# D_Output.net
KiCad netlist of a schematic drawn in Altium Designer
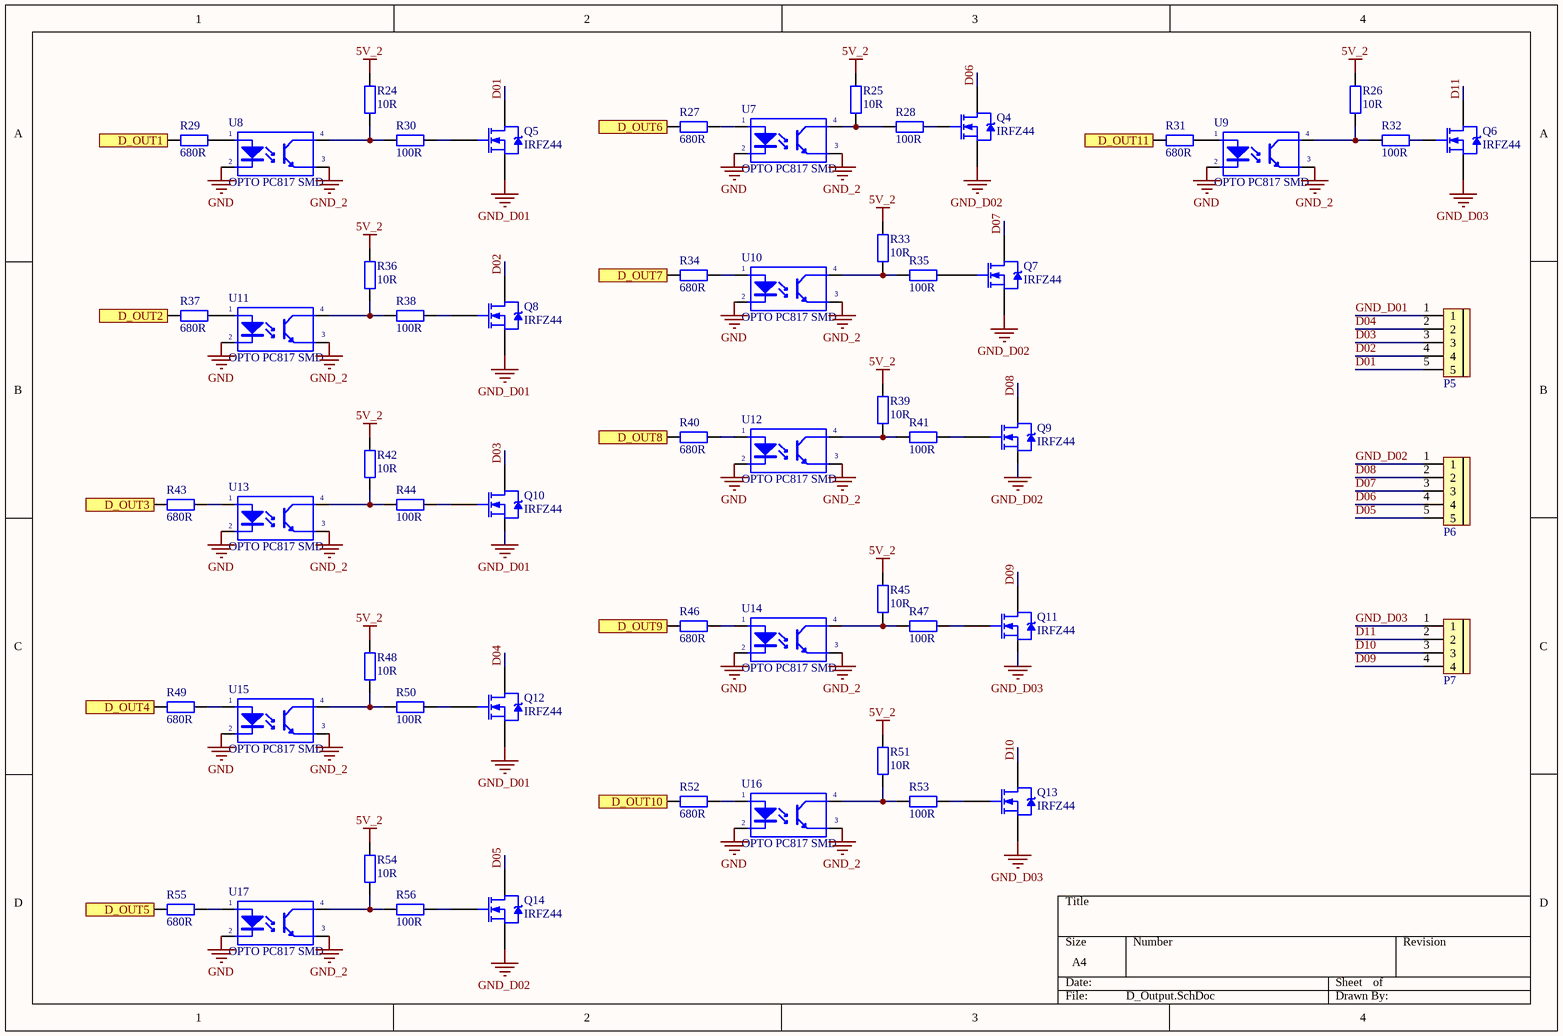
[diagram p0: D_Output.SchDoc]

(export (version "E")
  (design (tool "Eeschema 10.0.6"))
  (components
    (comp (ref "P5")
      (value "CON 5 EDG5.08")
      (footprint "CON 5 5EDG5.08")
      (description "Cắm")
      (libsource (lib "Altium_Lib_by_KhueNguyenCreator") (part "CON 5 EDG5.08"))
    )
    (comp (ref "P6")
      (value "CON 5 EDG5.08")
      (footprint "CON 5 5EDG5.08")
      (description "Cắm")
      (libsource (lib "Altium_Lib_by_KhueNguyenCreator") (part "CON 5 EDG5.08"))
    )
    (comp (ref "P7")
      (value "CON 4 EDG5.08")
      (footprint "CON 4 4EDG5.08")
      (description "Cắm")
      (libsource (lib "Altium_Lib_by_KhueNguyenCreator") (part "CON 4 EDG5.08"))
    )
    (comp (ref "Q4")
      (value "IRFZ44")
      (footprint "TO220")
      (description "N-Channel Power MOSFET")
      (libsource (lib "Altium_Lib_by_KhueNguyenCreator") (part "IRFZ44 DIP"))
    )
    (comp (ref "Q5")
      (value "IRFZ44")
      (footprint "TO220")
      (description "N-Channel Power MOSFET")
      (libsource (lib "Altium_Lib_by_KhueNguyenCreator") (part "IRFZ44 DIP"))
    )
    (comp (ref "Q6")
      (value "IRFZ44")
      (footprint "TO220")
      (description "N-Channel Power MOSFET")
      (libsource (lib "Altium_Lib_by_KhueNguyenCreator") (part "IRFZ44 DIP"))
    )
    (comp (ref "Q7")
      (value "IRFZ44")
      (footprint "TO220")
      (description "N-Channel Power MOSFET")
      (libsource (lib "Altium_Lib_by_KhueNguyenCreator") (part "IRFZ44 DIP"))
    )
    (comp (ref "Q8")
      (value "IRFZ44")
      (footprint "TO220")
      (description "N-Channel Power MOSFET")
      (libsource (lib "Altium_Lib_by_KhueNguyenCreator") (part "IRFZ44 DIP"))
    )
    (comp (ref "Q9")
      (value "IRFZ44")
      (footprint "TO220")
      (description "N-Channel Power MOSFET")
      (libsource (lib "Altium_Lib_by_KhueNguyenCreator") (part "IRFZ44 DIP"))
    )
    (comp (ref "Q10")
      (value "IRFZ44")
      (footprint "TO220")
      (description "N-Channel Power MOSFET")
      (libsource (lib "Altium_Lib_by_KhueNguyenCreator") (part "IRFZ44 DIP"))
    )
    (comp (ref "Q11")
      (value "IRFZ44")
      (footprint "TO220")
      (description "N-Channel Power MOSFET")
      (libsource (lib "Altium_Lib_by_KhueNguyenCreator") (part "IRFZ44 DIP"))
    )
    (comp (ref "Q12")
      (value "IRFZ44")
      (footprint "TO220")
      (description "N-Channel Power MOSFET")
      (libsource (lib "Altium_Lib_by_KhueNguyenCreator") (part "IRFZ44 DIP"))
    )
    (comp (ref "Q13")
      (value "IRFZ44")
      (footprint "TO220")
      (description "N-Channel Power MOSFET")
      (libsource (lib "Altium_Lib_by_KhueNguyenCreator") (part "IRFZ44 DIP"))
    )
    (comp (ref "Q14")
      (value "IRFZ44")
      (footprint "TO220")
      (description "N-Channel Power MOSFET")
      (libsource (lib "Altium_Lib_by_KhueNguyenCreator") (part "IRFZ44 DIP"))
    )
    (comp (ref "R24")
      (value "10R")
      (footprint "Tro smd 0603")
      (description "Dán")
      (libsource (lib "Altium_Lib_by_KhueNguyenCreator") (part "Tro 0603 5% 10R"))
    )
    (comp (ref "R25")
      (value "10R")
      (footprint "Tro smd 0603")
      (description "Dán")
      (libsource (lib "Altium_Lib_by_KhueNguyenCreator") (part "Tro 0603 5% 10R"))
    )
    (comp (ref "R26")
      (value "10R")
      (footprint "Tro smd 0603")
      (description "Dán")
      (libsource (lib "Altium_Lib_by_KhueNguyenCreator") (part "Tro 0603 5% 10R"))
    )
    (comp (ref "R27")
      (value "680R")
      (footprint "tro smd 0603")
      (description "Dán")
      (libsource (lib "Altium_Lib_by_KhueNguyenCreator") (part "Tro 0603 1% 680R"))
    )
    (comp (ref "R28")
      (value "100R")
      (footprint "tro smd 0603")
      (description "Dán")
      (libsource (lib "Altium_Lib_by_KhueNguyenCreator") (part "Tro 0603 5% 100R"))
    )
    (comp (ref "R29")
      (value "680R")
      (footprint "tro smd 0603")
      (description "Dán")
      (libsource (lib "Altium_Lib_by_KhueNguyenCreator") (part "Tro 0603 1% 680R"))
    )
    (comp (ref "R30")
      (value "100R")
      (footprint "tro smd 0603")
      (description "Dán")
      (libsource (lib "Altium_Lib_by_KhueNguyenCreator") (part "Tro 0603 5% 100R"))
    )
    (comp (ref "R31")
      (value "680R")
      (footprint "tro smd 0603")
      (description "Dán")
      (libsource (lib "Altium_Lib_by_KhueNguyenCreator") (part "Tro 0603 1% 680R"))
    )
    (comp (ref "R32")
      (value "100R")
      (footprint "tro smd 0603")
      (description "Dán")
      (libsource (lib "Altium_Lib_by_KhueNguyenCreator") (part "Tro 0603 5% 100R"))
    )
    (comp (ref "R33")
      (value "10R")
      (footprint "Tro smd 0603")
      (description "Dán")
      (libsource (lib "Altium_Lib_by_KhueNguyenCreator") (part "Tro 0603 5% 10R"))
    )
    (comp (ref "R34")
      (value "680R")
      (footprint "tro smd 0603")
      (description "Dán")
      (libsource (lib "Altium_Lib_by_KhueNguyenCreator") (part "Tro 0603 1% 680R"))
    )
    (comp (ref "R35")
      (value "100R")
      (footprint "tro smd 0603")
      (description "Dán")
      (libsource (lib "Altium_Lib_by_KhueNguyenCreator") (part "Tro 0603 5% 100R"))
    )
    (comp (ref "R36")
      (value "10R")
      (footprint "Tro smd 0603")
      (description "Dán")
      (libsource (lib "Altium_Lib_by_KhueNguyenCreator") (part "Tro 0603 5% 10R"))
    )
    (comp (ref "R37")
      (value "680R")
      (footprint "tro smd 0603")
      (description "Dán")
      (libsource (lib "Altium_Lib_by_KhueNguyenCreator") (part "Tro 0603 1% 680R"))
    )
    (comp (ref "R38")
      (value "100R")
      (footprint "tro smd 0603")
      (description "Dán")
      (libsource (lib "Altium_Lib_by_KhueNguyenCreator") (part "Tro 0603 5% 100R"))
    )
    (comp (ref "R39")
      (value "10R")
      (footprint "Tro smd 0603")
      (description "Dán")
      (libsource (lib "Altium_Lib_by_KhueNguyenCreator") (part "Tro 0603 5% 10R"))
    )
    (comp (ref "R40")
      (value "680R")
      (footprint "tro smd 0603")
      (description "Dán")
      (libsource (lib "Altium_Lib_by_KhueNguyenCreator") (part "Tro 0603 1% 680R"))
    )
    (comp (ref "R41")
      (value "100R")
      (footprint "tro smd 0603")
      (description "Dán")
      (libsource (lib "Altium_Lib_by_KhueNguyenCreator") (part "Tro 0603 5% 100R"))
    )
    (comp (ref "R42")
      (value "10R")
      (footprint "Tro smd 0603")
      (description "Dán")
      (libsource (lib "Altium_Lib_by_KhueNguyenCreator") (part "Tro 0603 5% 10R"))
    )
    (comp (ref "R43")
      (value "680R")
      (footprint "tro smd 0603")
      (description "Dán")
      (libsource (lib "Altium_Lib_by_KhueNguyenCreator") (part "Tro 0603 1% 680R"))
    )
    (comp (ref "R44")
      (value "100R")
      (footprint "tro smd 0603")
      (description "Dán")
      (libsource (lib "Altium_Lib_by_KhueNguyenCreator") (part "Tro 0603 5% 100R"))
    )
    (comp (ref "R45")
      (value "10R")
      (footprint "Tro smd 0603")
      (description "Dán")
      (libsource (lib "Altium_Lib_by_KhueNguyenCreator") (part "Tro 0603 5% 10R"))
    )
    (comp (ref "R46")
      (value "680R")
      (footprint "tro smd 0603")
      (description "Dán")
      (libsource (lib "Altium_Lib_by_KhueNguyenCreator") (part "Tro 0603 1% 680R"))
    )
    (comp (ref "R47")
      (value "100R")
      (footprint "tro smd 0603")
      (description "Dán")
      (libsource (lib "Altium_Lib_by_KhueNguyenCreator") (part "Tro 0603 5% 100R"))
    )
    (comp (ref "R48")
      (value "10R")
      (footprint "Tro smd 0603")
      (description "Dán")
      (libsource (lib "Altium_Lib_by_KhueNguyenCreator") (part "Tro 0603 5% 10R"))
    )
    (comp (ref "R49")
      (value "680R")
      (footprint "tro smd 0603")
      (description "Dán")
      (libsource (lib "Altium_Lib_by_KhueNguyenCreator") (part "Tro 0603 1% 680R"))
    )
    (comp (ref "R50")
      (value "100R")
      (footprint "tro smd 0603")
      (description "Dán")
      (libsource (lib "Altium_Lib_by_KhueNguyenCreator") (part "Tro 0603 5% 100R"))
    )
    (comp (ref "R51")
      (value "10R")
      (footprint "Tro smd 0603")
      (description "Dán")
      (libsource (lib "Altium_Lib_by_KhueNguyenCreator") (part "Tro 0603 5% 10R"))
    )
    (comp (ref "R52")
      (value "680R")
      (footprint "tro smd 0603")
      (description "Dán")
      (libsource (lib "Altium_Lib_by_KhueNguyenCreator") (part "Tro 0603 1% 680R"))
    )
    (comp (ref "R53")
      (value "100R")
      (footprint "tro smd 0603")
      (description "Dán")
      (libsource (lib "Altium_Lib_by_KhueNguyenCreator") (part "Tro 0603 5% 100R"))
    )
    (comp (ref "R54")
      (value "10R")
      (footprint "Tro smd 0603")
      (description "Dán")
      (libsource (lib "Altium_Lib_by_KhueNguyenCreator") (part "Tro 0603 5% 10R"))
    )
    (comp (ref "R55")
      (value "680R")
      (footprint "tro smd 0603")
      (description "Dán")
      (libsource (lib "Altium_Lib_by_KhueNguyenCreator") (part "Tro 0603 1% 680R"))
    )
    (comp (ref "R56")
      (value "100R")
      (footprint "tro smd 0603")
      (description "Dán")
      (libsource (lib "Altium_Lib_by_KhueNguyenCreator") (part "Tro 0603 5% 100R"))
    )
    (comp (ref "U7")
      (value "OPTO PC817 SMD")
      (footprint "SOP4")
      (description "Single Opto")
      (libsource (lib "Altium_Lib_by_KhueNguyenCreator") (part "OPTO PC817 SMD"))
    )
    (comp (ref "U8")
      (value "OPTO PC817 SMD")
      (footprint "SOP4")
      (description "Single Opto")
      (libsource (lib "Altium_Lib_by_KhueNguyenCreator") (part "OPTO PC817 SMD"))
    )
    (comp (ref "U9")
      (value "OPTO PC817 SMD")
      (footprint "SOP4")
      (description "Single Opto")
      (libsource (lib "Altium_Lib_by_KhueNguyenCreator") (part "OPTO PC817 SMD"))
    )
    (comp (ref "U10")
      (value "OPTO PC817 SMD")
      (footprint "SOP4")
      (description "Single Opto")
      (libsource (lib "Altium_Lib_by_KhueNguyenCreator") (part "OPTO PC817 SMD"))
    )
    (comp (ref "U11")
      (value "OPTO PC817 SMD")
      (footprint "SOP4")
      (description "Single Opto")
      (libsource (lib "Altium_Lib_by_KhueNguyenCreator") (part "OPTO PC817 SMD"))
    )
    (comp (ref "U12")
      (value "OPTO PC817 SMD")
      (footprint "SOP4")
      (description "Single Opto")
      (libsource (lib "Altium_Lib_by_KhueNguyenCreator") (part "OPTO PC817 SMD"))
    )
    (comp (ref "U13")
      (value "OPTO PC817 SMD")
      (footprint "SOP4")
      (description "Single Opto")
      (libsource (lib "Altium_Lib_by_KhueNguyenCreator") (part "OPTO PC817 SMD"))
    )
    (comp (ref "U14")
      (value "OPTO PC817 SMD")
      (footprint "SOP4")
      (description "Single Opto")
      (libsource (lib "Altium_Lib_by_KhueNguyenCreator") (part "OPTO PC817 SMD"))
    )
    (comp (ref "U15")
      (value "OPTO PC817 SMD")
      (footprint "SOP4")
      (description "Single Opto")
      (libsource (lib "Altium_Lib_by_KhueNguyenCreator") (part "OPTO PC817 SMD"))
    )
    (comp (ref "U16")
      (value "OPTO PC817 SMD")
      (footprint "SOP4")
      (description "Single Opto")
      (libsource (lib "Altium_Lib_by_KhueNguyenCreator") (part "OPTO PC817 SMD"))
    )
    (comp (ref "U17")
      (value "OPTO PC817 SMD")
      (footprint "SOP4")
      (description "Single Opto")
      (libsource (lib "Altium_Lib_by_KhueNguyenCreator") (part "OPTO PC817 SMD"))
    )
  )
  (nets
    (net (code "1") (name "/D01") (class "Default")
      (node (ref "P5") (pin "5") (pinfunction "5_5") (pintype "passive"))
      (node (ref "Q5") (pin "2") (pinfunction "D_2") (pintype "passive"))
    )
    (net (code "2") (name "/D02") (class "Default")
      (node (ref "P5") (pin "4") (pinfunction "4_4") (pintype "passive"))
      (node (ref "Q8") (pin "2") (pinfunction "D_2") (pintype "passive"))
    )
    (net (code "3") (name "/D03") (class "Default")
      (node (ref "P5") (pin "3") (pinfunction "3_3") (pintype "passive"))
      (node (ref "Q10") (pin "2") (pinfunction "D_2") (pintype "passive"))
    )
    (net (code "4") (name "/D04") (class "Default")
      (node (ref "P5") (pin "2") (pinfunction "2_2") (pintype "passive"))
      (node (ref "Q12") (pin "2") (pinfunction "D_2") (pintype "passive"))
    )
    (net (code "5") (name "/D05") (class "Default")
      (node (ref "P6") (pin "5") (pinfunction "5_5") (pintype "passive"))
      (node (ref "Q14") (pin "2") (pinfunction "D_2") (pintype "passive"))
    )
    (net (code "6") (name "/D06") (class "Default")
      (node (ref "P6") (pin "4") (pinfunction "4_4") (pintype "passive"))
      (node (ref "Q4") (pin "2") (pinfunction "D_2") (pintype "passive"))
    )
    (net (code "7") (name "/D07") (class "Default")
      (node (ref "P6") (pin "3") (pinfunction "3_3") (pintype "passive"))
      (node (ref "Q7") (pin "2") (pinfunction "D_2") (pintype "passive"))
    )
    (net (code "8") (name "/D08") (class "Default")
      (node (ref "P6") (pin "2") (pinfunction "2_2") (pintype "passive"))
      (node (ref "Q9") (pin "2") (pinfunction "D_2") (pintype "passive"))
    )
    (net (code "9") (name "/D09") (class "Default")
      (node (ref "P7") (pin "4") (pinfunction "4_4") (pintype "passive"))
      (node (ref "Q11") (pin "2") (pinfunction "D_2") (pintype "passive"))
    )
    (net (code "10") (name "/D10") (class "Default")
      (node (ref "P7") (pin "3") (pinfunction "3_3") (pintype "passive"))
      (node (ref "Q13") (pin "2") (pinfunction "D_2") (pintype "passive"))
    )
    (net (code "11") (name "/D11") (class "Default")
      (node (ref "P7") (pin "2") (pinfunction "2_2") (pintype "passive"))
      (node (ref "Q6") (pin "2") (pinfunction "D_2") (pintype "passive"))
    )
    (net (code "12") (name "/D_OUT1") (class "Default")
      (node (ref "R29") (pin "1") (pinfunction "1_1") (pintype "passive"))
    )
    (net (code "13") (name "/D_OUT2") (class "Default")
      (node (ref "R37") (pin "1") (pinfunction "1_1") (pintype "passive"))
    )
    (net (code "14") (name "/D_OUT3") (class "Default")
      (node (ref "R43") (pin "1") (pinfunction "1_1") (pintype "passive"))
    )
    (net (code "15") (name "/D_OUT4") (class "Default")
      (node (ref "R49") (pin "1") (pinfunction "1_1") (pintype "passive"))
    )
    (net (code "16") (name "/D_OUT5") (class "Default")
      (node (ref "R55") (pin "1") (pinfunction "1_1") (pintype "passive"))
    )
    (net (code "17") (name "/D_OUT6") (class "Default")
      (node (ref "R27") (pin "1") (pinfunction "1_1") (pintype "passive"))
    )
    (net (code "18") (name "/D_OUT7") (class "Default")
      (node (ref "R34") (pin "1") (pinfunction "1_1") (pintype "passive"))
    )
    (net (code "19") (name "/D_OUT8") (class "Default")
      (node (ref "R40") (pin "1") (pinfunction "1_1") (pintype "passive"))
    )
    (net (code "20") (name "/D_OUT9") (class "Default")
      (node (ref "R46") (pin "1") (pinfunction "1_1") (pintype "passive"))
    )
    (net (code "21") (name "/D_OUT10") (class "Default")
      (node (ref "R52") (pin "1") (pinfunction "1_1") (pintype "passive"))
    )
    (net (code "22") (name "/D_OUT11") (class "Default")
      (node (ref "R31") (pin "1") (pinfunction "1_1") (pintype "passive"))
    )
    (net (code "23") (name "5V_2") (class "Default")
      (node (ref "R24") (pin "2") (pinfunction "2_2") (pintype "passive"))
      (node (ref "R25") (pin "2") (pinfunction "2_2") (pintype "passive"))
      (node (ref "R26") (pin "2") (pinfunction "2_2") (pintype "passive"))
      (node (ref "R33") (pin "2") (pinfunction "2_2") (pintype "passive"))
      (node (ref "R36") (pin "2") (pinfunction "2_2") (pintype "passive"))
      (node (ref "R39") (pin "2") (pinfunction "2_2") (pintype "passive"))
      (node (ref "R42") (pin "2") (pinfunction "2_2") (pintype "passive"))
      (node (ref "R45") (pin "2") (pinfunction "2_2") (pintype "passive"))
      (node (ref "R48") (pin "2") (pinfunction "2_2") (pintype "passive"))
      (node (ref "R51") (pin "2") (pinfunction "2_2") (pintype "passive"))
      (node (ref "R54") (pin "2") (pinfunction "2_2") (pintype "passive"))
    )
    (net (code "24") (name "GND") (class "Default")
      (node (ref "U10") (pin "2") (pinfunction "K_2") (pintype "passive"))
      (node (ref "U11") (pin "2") (pinfunction "K_2") (pintype "passive"))
      (node (ref "U12") (pin "2") (pinfunction "K_2") (pintype "passive"))
      (node (ref "U13") (pin "2") (pinfunction "K_2") (pintype "passive"))
      (node (ref "U14") (pin "2") (pinfunction "K_2") (pintype "passive"))
      (node (ref "U15") (pin "2") (pinfunction "K_2") (pintype "passive"))
      (node (ref "U16") (pin "2") (pinfunction "K_2") (pintype "passive"))
      (node (ref "U17") (pin "2") (pinfunction "K_2") (pintype "passive"))
      (node (ref "U7") (pin "2") (pinfunction "K_2") (pintype "passive"))
      (node (ref "U8") (pin "2") (pinfunction "K_2") (pintype "passive"))
      (node (ref "U9") (pin "2") (pinfunction "K_2") (pintype "passive"))
    )
    (net (code "25") (name "GND_2") (class "Default")
      (node (ref "U10") (pin "3") (pinfunction "E_3") (pintype "passive"))
      (node (ref "U11") (pin "3") (pinfunction "E_3") (pintype "passive"))
      (node (ref "U12") (pin "3") (pinfunction "E_3") (pintype "passive"))
      (node (ref "U13") (pin "3") (pinfunction "E_3") (pintype "passive"))
      (node (ref "U14") (pin "3") (pinfunction "E_3") (pintype "passive"))
      (node (ref "U15") (pin "3") (pinfunction "E_3") (pintype "passive"))
      (node (ref "U16") (pin "3") (pinfunction "E_3") (pintype "passive"))
      (node (ref "U17") (pin "3") (pinfunction "E_3") (pintype "passive"))
      (node (ref "U7") (pin "3") (pinfunction "E_3") (pintype "passive"))
      (node (ref "U8") (pin "3") (pinfunction "E_3") (pintype "passive"))
      (node (ref "U9") (pin "3") (pinfunction "E_3") (pintype "passive"))
    )
    (net (code "26") (name "GND_D01") (class "Default")
      (node (ref "P5") (pin "1") (pinfunction "1_1") (pintype "passive"))
      (node (ref "Q10") (pin "3") (pinfunction "S_3") (pintype "passive"))
      (node (ref "Q12") (pin "3") (pinfunction "S_3") (pintype "passive"))
      (node (ref "Q5") (pin "3") (pinfunction "S_3") (pintype "passive"))
      (node (ref "Q8") (pin "3") (pinfunction "S_3") (pintype "passive"))
    )
    (net (code "27") (name "GND_D02") (class "Default")
      (node (ref "P6") (pin "1") (pinfunction "1_1") (pintype "passive"))
      (node (ref "Q14") (pin "3") (pinfunction "S_3") (pintype "passive"))
      (node (ref "Q4") (pin "3") (pinfunction "S_3") (pintype "passive"))
      (node (ref "Q7") (pin "3") (pinfunction "S_3") (pintype "passive"))
      (node (ref "Q9") (pin "3") (pinfunction "S_3") (pintype "passive"))
    )
    (net (code "28") (name "GND_D03") (class "Default")
      (node (ref "P7") (pin "1") (pinfunction "1_1") (pintype "passive"))
      (node (ref "Q11") (pin "3") (pinfunction "S_3") (pintype "passive"))
      (node (ref "Q13") (pin "3") (pinfunction "S_3") (pintype "passive"))
      (node (ref "Q6") (pin "3") (pinfunction "S_3") (pintype "passive"))
    )
    (net (code "29") (name "Net-(Q4-G)") (class "Default")
      (node (ref "Q4") (pin "1") (pinfunction "G_1") (pintype "passive"))
      (node (ref "R28") (pin "2") (pinfunction "2_2") (pintype "passive"))
    )
    (net (code "30") (name "Net-(Q5-G)") (class "Default")
      (node (ref "Q5") (pin "1") (pinfunction "G_1") (pintype "passive"))
      (node (ref "R30") (pin "2") (pinfunction "2_2") (pintype "passive"))
    )
    (net (code "31") (name "Net-(Q6-G)") (class "Default")
      (node (ref "Q6") (pin "1") (pinfunction "G_1") (pintype "passive"))
      (node (ref "R32") (pin "2") (pinfunction "2_2") (pintype "passive"))
    )
    (net (code "32") (name "Net-(Q7-G)") (class "Default")
      (node (ref "Q7") (pin "1") (pinfunction "G_1") (pintype "passive"))
      (node (ref "R35") (pin "2") (pinfunction "2_2") (pintype "passive"))
    )
    (net (code "33") (name "Net-(Q8-G)") (class "Default")
      (node (ref "Q8") (pin "1") (pinfunction "G_1") (pintype "passive"))
      (node (ref "R38") (pin "2") (pinfunction "2_2") (pintype "passive"))
    )
    (net (code "34") (name "Net-(Q9-G)") (class "Default")
      (node (ref "Q9") (pin "1") (pinfunction "G_1") (pintype "passive"))
      (node (ref "R41") (pin "2") (pinfunction "2_2") (pintype "passive"))
    )
    (net (code "35") (name "Net-(Q10-G)") (class "Default")
      (node (ref "Q10") (pin "1") (pinfunction "G_1") (pintype "passive"))
      (node (ref "R44") (pin "2") (pinfunction "2_2") (pintype "passive"))
    )
    (net (code "36") (name "Net-(Q11-G)") (class "Default")
      (node (ref "Q11") (pin "1") (pinfunction "G_1") (pintype "passive"))
      (node (ref "R47") (pin "2") (pinfunction "2_2") (pintype "passive"))
    )
    (net (code "37") (name "Net-(Q12-G)") (class "Default")
      (node (ref "Q12") (pin "1") (pinfunction "G_1") (pintype "passive"))
      (node (ref "R50") (pin "2") (pinfunction "2_2") (pintype "passive"))
    )
    (net (code "38") (name "Net-(Q13-G)") (class "Default")
      (node (ref "Q13") (pin "1") (pinfunction "G_1") (pintype "passive"))
      (node (ref "R53") (pin "2") (pinfunction "2_2") (pintype "passive"))
    )
    (net (code "39") (name "Net-(Q14-G)") (class "Default")
      (node (ref "Q14") (pin "1") (pinfunction "G_1") (pintype "passive"))
      (node (ref "R56") (pin "2") (pinfunction "2_2") (pintype "passive"))
    )
    (net (code "40") (name "Net-(U7-A)") (class "Default")
      (node (ref "R27") (pin "2") (pinfunction "2_2") (pintype "passive"))
      (node (ref "U7") (pin "1") (pinfunction "A_1") (pintype "passive"))
    )
    (net (code "41") (name "Net-(U7-C)") (class "Default")
      (node (ref "R25") (pin "1") (pinfunction "1_1") (pintype "passive"))
      (node (ref "R28") (pin "1") (pinfunction "1_1") (pintype "passive"))
      (node (ref "U7") (pin "4") (pinfunction "C_4") (pintype "passive"))
    )
    (net (code "42") (name "Net-(U8-A)") (class "Default")
      (node (ref "R29") (pin "2") (pinfunction "2_2") (pintype "passive"))
      (node (ref "U8") (pin "1") (pinfunction "A_1") (pintype "passive"))
    )
    (net (code "43") (name "Net-(U8-C)") (class "Default")
      (node (ref "R24") (pin "1") (pinfunction "1_1") (pintype "passive"))
      (node (ref "R30") (pin "1") (pinfunction "1_1") (pintype "passive"))
      (node (ref "U8") (pin "4") (pinfunction "C_4") (pintype "passive"))
    )
    (net (code "44") (name "Net-(U9-A)") (class "Default")
      (node (ref "R31") (pin "2") (pinfunction "2_2") (pintype "passive"))
      (node (ref "U9") (pin "1") (pinfunction "A_1") (pintype "passive"))
    )
    (net (code "45") (name "Net-(U9-C)") (class "Default")
      (node (ref "R26") (pin "1") (pinfunction "1_1") (pintype "passive"))
      (node (ref "R32") (pin "1") (pinfunction "1_1") (pintype "passive"))
      (node (ref "U9") (pin "4") (pinfunction "C_4") (pintype "passive"))
    )
    (net (code "46") (name "Net-(U10-A)") (class "Default")
      (node (ref "R34") (pin "2") (pinfunction "2_2") (pintype "passive"))
      (node (ref "U10") (pin "1") (pinfunction "A_1") (pintype "passive"))
    )
    (net (code "47") (name "Net-(U10-C)") (class "Default")
      (node (ref "R33") (pin "1") (pinfunction "1_1") (pintype "passive"))
      (node (ref "R35") (pin "1") (pinfunction "1_1") (pintype "passive"))
      (node (ref "U10") (pin "4") (pinfunction "C_4") (pintype "passive"))
    )
    (net (code "48") (name "Net-(U11-A)") (class "Default")
      (node (ref "R37") (pin "2") (pinfunction "2_2") (pintype "passive"))
      (node (ref "U11") (pin "1") (pinfunction "A_1") (pintype "passive"))
    )
    (net (code "49") (name "Net-(U11-C)") (class "Default")
      (node (ref "R36") (pin "1") (pinfunction "1_1") (pintype "passive"))
      (node (ref "R38") (pin "1") (pinfunction "1_1") (pintype "passive"))
      (node (ref "U11") (pin "4") (pinfunction "C_4") (pintype "passive"))
    )
    (net (code "50") (name "Net-(U12-A)") (class "Default")
      (node (ref "R40") (pin "2") (pinfunction "2_2") (pintype "passive"))
      (node (ref "U12") (pin "1") (pinfunction "A_1") (pintype "passive"))
    )
    (net (code "51") (name "Net-(U12-C)") (class "Default")
      (node (ref "R39") (pin "1") (pinfunction "1_1") (pintype "passive"))
      (node (ref "R41") (pin "1") (pinfunction "1_1") (pintype "passive"))
      (node (ref "U12") (pin "4") (pinfunction "C_4") (pintype "passive"))
    )
    (net (code "52") (name "Net-(U13-A)") (class "Default")
      (node (ref "R43") (pin "2") (pinfunction "2_2") (pintype "passive"))
      (node (ref "U13") (pin "1") (pinfunction "A_1") (pintype "passive"))
    )
    (net (code "53") (name "Net-(U13-C)") (class "Default")
      (node (ref "R42") (pin "1") (pinfunction "1_1") (pintype "passive"))
      (node (ref "R44") (pin "1") (pinfunction "1_1") (pintype "passive"))
      (node (ref "U13") (pin "4") (pinfunction "C_4") (pintype "passive"))
    )
    (net (code "54") (name "Net-(U14-A)") (class "Default")
      (node (ref "R46") (pin "2") (pinfunction "2_2") (pintype "passive"))
      (node (ref "U14") (pin "1") (pinfunction "A_1") (pintype "passive"))
    )
    (net (code "55") (name "Net-(U14-C)") (class "Default")
      (node (ref "R45") (pin "1") (pinfunction "1_1") (pintype "passive"))
      (node (ref "R47") (pin "1") (pinfunction "1_1") (pintype "passive"))
      (node (ref "U14") (pin "4") (pinfunction "C_4") (pintype "passive"))
    )
    (net (code "56") (name "Net-(U15-A)") (class "Default")
      (node (ref "R49") (pin "2") (pinfunction "2_2") (pintype "passive"))
      (node (ref "U15") (pin "1") (pinfunction "A_1") (pintype "passive"))
    )
    (net (code "57") (name "Net-(U15-C)") (class "Default")
      (node (ref "R48") (pin "1") (pinfunction "1_1") (pintype "passive"))
      (node (ref "R50") (pin "1") (pinfunction "1_1") (pintype "passive"))
      (node (ref "U15") (pin "4") (pinfunction "C_4") (pintype "passive"))
    )
    (net (code "58") (name "Net-(U16-A)") (class "Default")
      (node (ref "R52") (pin "2") (pinfunction "2_2") (pintype "passive"))
      (node (ref "U16") (pin "1") (pinfunction "A_1") (pintype "passive"))
    )
    (net (code "59") (name "Net-(U16-C)") (class "Default")
      (node (ref "R51") (pin "1") (pinfunction "1_1") (pintype "passive"))
      (node (ref "R53") (pin "1") (pinfunction "1_1") (pintype "passive"))
      (node (ref "U16") (pin "4") (pinfunction "C_4") (pintype "passive"))
    )
    (net (code "60") (name "Net-(U17-A)") (class "Default")
      (node (ref "R55") (pin "2") (pinfunction "2_2") (pintype "passive"))
      (node (ref "U17") (pin "1") (pinfunction "A_1") (pintype "passive"))
    )
    (net (code "61") (name "Net-(U17-C)") (class "Default")
      (node (ref "R54") (pin "1") (pinfunction "1_1") (pintype "passive"))
      (node (ref "R56") (pin "1") (pinfunction "1_1") (pintype "passive"))
      (node (ref "U17") (pin "4") (pinfunction "C_4") (pintype "passive"))
    )
  )
)
